# ConditioningBoard_BSPD_V1_0.net
KiCad netlist of a schematic drawn in Altium Designer
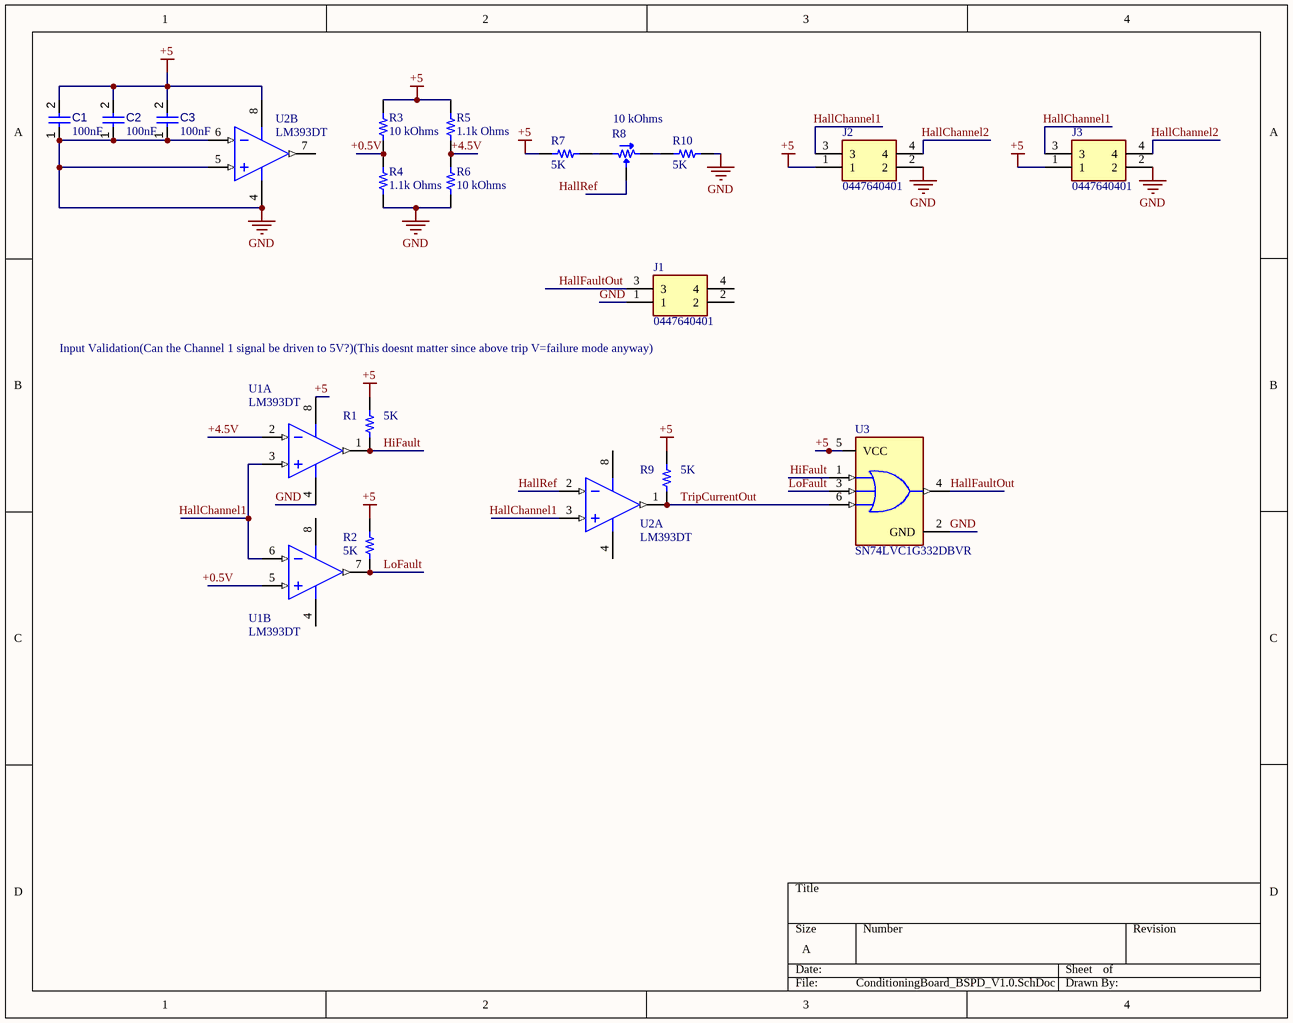
[diagram p0: ConditioningBoard_BSPD_V1.0.SchDoc]

(export (version "E")
  (design (tool "Eeschema 10.0.6"))
  (components
    (comp (ref "C1")
      (value "100nF")
      (footprint "CAPC1608X90X40NL10T20")
      (description "Chip Capacitor, 100 nF, +/- 10%, 50 V, 0603 (1608 Metric)")
      (fields (field (name "TOLERANCE") "10%") (field (name "Comment") "Capacitor 100 nF +/-10% 50 V 0603"))
      (libsource (lib "Kennesaw Motorsports") (part "CAP-NP-2"))
    )
    (comp (ref "C2")
      (value "100nF")
      (footprint "CAPC1608X90X40NL10T20")
      (description "Chip Capacitor, 100 nF, +/- 10%, 50 V, 0603 (1608 Metric)")
      (fields (field (name "TOLERANCE") "10%") (field (name "Comment") "Capacitor 100 nF +/-10% 50 V 0603"))
      (libsource (lib "Kennesaw Motorsports") (part "CAP-NP-2"))
    )
    (comp (ref "C3")
      (value "100nF")
      (footprint "CAPC1608X90X40NL10T20")
      (description "Chip Capacitor, 100 nF, +/- 10%, 50 V, 0603 (1608 Metric)")
      (fields (field (name "TOLERANCE") "10%") (field (name "Comment") "Capacitor 100 nF +/-10% 50 V 0603"))
      (libsource (lib "Kennesaw Motorsports") (part "CAP-NP-2"))
    )
    (comp (ref "J1")
      (value "0447640401")
      (footprint "SamacSys:0447640401")
      (description "Connector")
      (libsource (lib "*") (part "0447640401"))
    )
    (comp (ref "J2")
      (value "0447640401")
      (footprint "SamacSys:0447640401")
      (description "Connector")
      (libsource (lib "*") (part "0447640401"))
    )
    (comp (ref "J3")
      (value "0447640401")
      (footprint "SamacSys:0447640401")
      (description "Connector")
      (libsource (lib "*") (part "0447640401"))
    )
    (comp (ref "R1")
      (value "5K")
      (footprint "RES 0603_1608")
      (description "CRGP 0603 5K6 1%")
      (fields
        (field (name "PART NUMBER") "CRGP0603F5K6")
        (field (name "MANUFACTURER") "TE Connectivity Passive Product")
      )
      (libsource (lib "Celestial Altium Library - altium_library") (part "Resistor"))
    )
    (comp (ref "R2")
      (value "5K")
      (footprint "RES 0603_1608")
      (description "CRGP 0603 5K6 1%")
      (fields
        (field (name "PART NUMBER") "CRGP0603F5K6")
        (field (name "MANUFACTURER") "TE Connectivity Passive Product")
      )
      (libsource (lib "Celestial Altium Library - altium_library") (part "Resistor"))
    )
    (comp (ref "R3")
      (value "10 kOhms")
      (footprint "RES 0603_1608")
      (description "RES SMD 10K OHM 0.1% 1/16W 0603")
      (fields
        (field (name "PART NUMBER") "CPF0603B10KE")
        (field (name "MANUFACTURER") "TE Connectivity Passive Product")
      )
      (libsource (lib "Celestial Altium Library - altium_library") (part "Resistor"))
    )
    (comp (ref "R4")
      (value "1.1k Ohms")
      (footprint "RES 0603_1608")
      (description "RES 442 OHM 1% 1/8W 0603")
      (fields
        (field (name "PART NUMBER") "RK73H1JTTD4420F")
        (field (name "MANUFACTURER") "KOA Speer Electronics, Inc.")
      )
      (libsource (lib "Celestial Altium Library - altium_library") (part "Resistor"))
    )
    (comp (ref "R5")
      (value "1.1k Ohms")
      (footprint "RES 0603_1608")
      (description "RES 442 OHM 1% 1/8W 0603")
      (fields
        (field (name "PART NUMBER") "RK73H1JTTD4420F")
        (field (name "MANUFACTURER") "KOA Speer Electronics, Inc.")
      )
      (libsource (lib "Celestial Altium Library - altium_library") (part "Resistor"))
    )
    (comp (ref "R6")
      (value "10 kOhms")
      (footprint "RES 0603_1608")
      (description "RES SMD 10K OHM 0.1% 1/16W 0603")
      (fields
        (field (name "PART NUMBER") "CPF0603B10KE")
        (field (name "MANUFACTURER") "TE Connectivity Passive Product")
      )
      (libsource (lib "Celestial Altium Library - altium_library") (part "Resistor"))
    )
    (comp (ref "R7")
      (value "5K")
      (footprint "RES 0603_1608")
      (description "CRGP 0603 5K6 1%")
      (fields
        (field (name "PART NUMBER") "CRGP0603F5K6")
        (field (name "MANUFACTURER") "TE Connectivity Passive Product")
      )
      (libsource (lib "Celestial Altium Library - altium_library") (part "Resistor"))
    )
    (comp (ref "R8")
      (value "10 kOhms")
      (footprint "POT BOURNS TRIMPOT TC33")
      (description "TRIMMER 10K OHM 0.1W J LEAD TOP")
      (fields (field (name "PART NUMBER") "TC33X-2-103E") (field (name "MANUFACTURER") "Bourns Inc."))
      (libsource (lib "Celestial Altium Library - altium_library") (part "Potentiometer"))
    )
    (comp (ref "R9")
      (value "5K")
      (footprint "RES 0603_1608")
      (description "CRGP 0603 5K6 1%")
      (fields
        (field (name "PART NUMBER") "CRGP0603F5K6")
        (field (name "MANUFACTURER") "TE Connectivity Passive Product")
      )
      (libsource (lib "Celestial Altium Library - altium_library") (part "Resistor"))
    )
    (comp (ref "R10")
      (value "5K")
      (footprint "RES 0603_1608")
      (description "CRGP 0603 5K6 1%")
      (fields
        (field (name "PART NUMBER") "CRGP0603F5K6")
        (field (name "MANUFACTURER") "TE Connectivity Passive Product")
      )
      (libsource (lib "Celestial Altium Library - altium_library") (part "Resistor"))
    )
    (comp (ref "U1")
      (value "LM393DT")
      (footprint "STM-SO-8_D_L")
      (description "Low-Power, Dual-Voltage Comparator, 2 to 36 V, 0 to 70 degC, 8-Pin SOIC (SO), RoHS, Tape and Reel")
      (fields (field (name "MANUFACTURER") "STMicroelectronics"))
      (libsource (lib "Altium Content Vault") (part "STM-LM393-SO8"))
    )
    (comp (ref "U2")
      (value "LM393DT")
      (footprint "STM-SO-8_D_L")
      (description "Low-Power, Dual-Voltage Comparator, 2 to 36 V, 0 to 70 degC, 8-Pin SOIC (SO), RoHS, Tape and Reel")
      (fields (field (name "MANUFACTURER") "STMicroelectronics"))
      (libsource (lib "Altium Content Vault") (part "STM-LM393-SO8"))
    )
    (comp (ref "U3")
      (value "SN74LVC1G332DBVR")
      (footprint "FP-DBV0006A-MFG")
      (description "OR Gate IC 1 Channel  SOT-23-6")
      (fields (field (name "OCTOPART") "https://octopart.com/sn74lvc1g332dbvr-texas+instruments-464996"))
      (libsource (lib "Altium Content Vault") (part "9bd6587d4ded7f3f3ab4f7d0d680d6b"))
    )
  )
  (nets
    (net (code "1") (name "+5") (class "Default")
      (node (ref "C1") (pin "2") (pinfunction "2_2") (pintype "passive"))
      (node (ref "C2") (pin "2") (pinfunction "2_2") (pintype "passive"))
      (node (ref "C3") (pin "2") (pinfunction "2_2") (pintype "passive"))
      (node (ref "J2") (pin "1") (pinfunction "1_1") (pintype "passive"))
      (node (ref "J3") (pin "1") (pinfunction "1_1") (pintype "passive"))
      (node (ref "R1") (pin "1") (pinfunction "1_1") (pintype "passive"))
      (node (ref "R2") (pin "1") (pinfunction "1_1") (pintype "passive"))
      (node (ref "R3") (pin "2") (pinfunction "2_2") (pintype "passive"))
      (node (ref "R5") (pin "1") (pinfunction "1_1") (pintype "passive"))
      (node (ref "R7") (pin "1") (pinfunction "1_1") (pintype "passive"))
      (node (ref "R9") (pin "1") (pinfunction "1_1") (pintype "passive"))
      (node (ref "U1") (pin "8") (pinfunction "VCC+_8") (pintype "power_in"))
      (node (ref "U2") (pin "8") (pinfunction "VCC+_8") (pintype "power_in"))
      (node (ref "U3") (pin "5") (pinfunction "VCC_5") (pintype "power_in"))
    )
    (net (code "2") (name "/+0.5V") (class "Default")
      (node (ref "R3") (pin "1") (pinfunction "1_1") (pintype "passive"))
      (node (ref "R4") (pin "2") (pinfunction "2_2") (pintype "passive"))
      (node (ref "U1") (pin "5") (pinfunction "IN2+_5") (pintype "input"))
    )
    (net (code "3") (name "/+4.5V") (class "Default")
      (node (ref "R5") (pin "2") (pinfunction "2_2") (pintype "passive"))
      (node (ref "R6") (pin "2") (pinfunction "2_2") (pintype "passive"))
      (node (ref "U1") (pin "2") (pinfunction "IN1-_2") (pintype "input"))
    )
    (net (code "4") (name "/HallChannel1") (class "Default")
      (node (ref "J2") (pin "3") (pinfunction "3_3") (pintype "passive"))
      (node (ref "J3") (pin "3") (pinfunction "3_3") (pintype "passive"))
      (node (ref "U1") (pin "3") (pinfunction "IN1+_3") (pintype "input"))
      (node (ref "U1") (pin "6") (pinfunction "IN2-_6") (pintype "input"))
      (node (ref "U2") (pin "3") (pinfunction "IN1+_3") (pintype "input"))
    )
    (net (code "5") (name "/HallChannel2") (class "Default")
      (node (ref "J2") (pin "4") (pinfunction "4_4") (pintype "passive"))
      (node (ref "J3") (pin "4") (pinfunction "4_4") (pintype "passive"))
    )
    (net (code "6") (name "/HallFaultOut") (class "Default")
      (node (ref "J1") (pin "3") (pinfunction "3_3") (pintype "passive"))
      (node (ref "U3") (pin "4") (pinfunction "Y_4") (pintype "output"))
    )
    (net (code "7") (name "/HallRef") (class "Default")
      (node (ref "R8") (pin "2") (pinfunction "2_2") (pintype "passive"))
      (node (ref "U2") (pin "2") (pinfunction "IN1-_2") (pintype "input"))
    )
    (net (code "8") (name "/HiFault") (class "Default")
      (node (ref "R1") (pin "2") (pinfunction "2_2") (pintype "passive"))
      (node (ref "U1") (pin "1") (pinfunction "OUT1_1") (pintype "output"))
      (node (ref "U3") (pin "1") (pinfunction "A_1") (pintype "input"))
    )
    (net (code "9") (name "/LoFault") (class "Default")
      (node (ref "R2") (pin "2") (pinfunction "2_2") (pintype "passive"))
      (node (ref "U1") (pin "7") (pinfunction "OUT2_7") (pintype "output"))
      (node (ref "U3") (pin "3") (pinfunction "B_3") (pintype "input"))
    )
    (net (code "10") (name "/TripCurrentOut") (class "Default")
      (node (ref "R9") (pin "2") (pinfunction "2_2") (pintype "passive"))
      (node (ref "U2") (pin "1") (pinfunction "OUT1_1") (pintype "output"))
      (node (ref "U3") (pin "6") (pinfunction "C_6") (pintype "input"))
    )
    (net (code "11") (name "GND") (class "Default")
      (node (ref "C1") (pin "1") (pinfunction "1_1") (pintype "passive"))
      (node (ref "C2") (pin "1") (pinfunction "1_1") (pintype "passive"))
      (node (ref "C3") (pin "1") (pinfunction "1_1") (pintype "passive"))
      (node (ref "J1") (pin "1") (pinfunction "1_1") (pintype "passive"))
      (node (ref "J2") (pin "2") (pinfunction "2_2") (pintype "passive"))
      (node (ref "J3") (pin "2") (pinfunction "2_2") (pintype "passive"))
      (node (ref "R10") (pin "1") (pinfunction "1_1") (pintype "passive"))
      (node (ref "R4") (pin "1") (pinfunction "1_1") (pintype "passive"))
      (node (ref "R6") (pin "1") (pinfunction "1_1") (pintype "passive"))
      (node (ref "U1") (pin "4") (pinfunction "VCC-_4") (pintype "power_in"))
      (node (ref "U2") (pin "4") (pinfunction "VCC-_4") (pintype "power_in"))
      (node (ref "U2") (pin "5") (pinfunction "IN2+_5") (pintype "input"))
      (node (ref "U2") (pin "6") (pinfunction "IN2-_6") (pintype "input"))
      (node (ref "U3") (pin "2") (pinfunction "GND_2") (pintype "power_in"))
    )
    (net (code "12") (name "Net-(R7-Pad2)") (class "Default")
      (node (ref "R7") (pin "2") (pinfunction "2_2") (pintype "passive"))
      (node (ref "R8") (pin "1") (pinfunction "1_1") (pintype "passive"))
    )
    (net (code "13") (name "Net-(R10-Pad2)") (class "Default")
      (node (ref "R10") (pin "2") (pinfunction "2_2") (pintype "passive"))
      (node (ref "R8") (pin "3") (pinfunction "3_3") (pintype "passive"))
    )
    (net (code "14") (name "unconnected-(J1-Pad2)") (class "Default")
      (node (ref "J1") (pin "2") (pinfunction "2_2") (pintype "passive"))
    )
    (net (code "15") (name "unconnected-(J1-Pad4)") (class "Default")
      (node (ref "J1") (pin "4") (pinfunction "4_4") (pintype "passive"))
    )
    (net (code "16") (name "unconnected-(U1B-VCC+-Pad8)") (class "Default")
      (node (ref "U1") (pin "8") (pinfunction "VCC+_8") (pintype "power_in"))
    )
    (net (code "17") (name "unconnected-(U1B-VCC--Pad4)") (class "Default")
      (node (ref "U1") (pin "4") (pinfunction "VCC-_4") (pintype "power_in"))
    )
    (net (code "18") (name "unconnected-(U2A-VCC+-Pad8)") (class "Default")
      (node (ref "U2") (pin "8") (pinfunction "VCC+_8") (pintype "power_in"))
    )
    (net (code "19") (name "unconnected-(U2A-VCC--Pad4)") (class "Default")
      (node (ref "U2") (pin "4") (pinfunction "VCC-_4") (pintype "power_in"))
    )
    (net (code "20") (name "unconnected-(U2B-OUT2-Pad7)") (class "Default")
      (node (ref "U2") (pin "7") (pinfunction "OUT2_7") (pintype "output"))
    )
  )
)
